# Layer_4.net
KiCad netlist of a schematic drawn in EAGLE
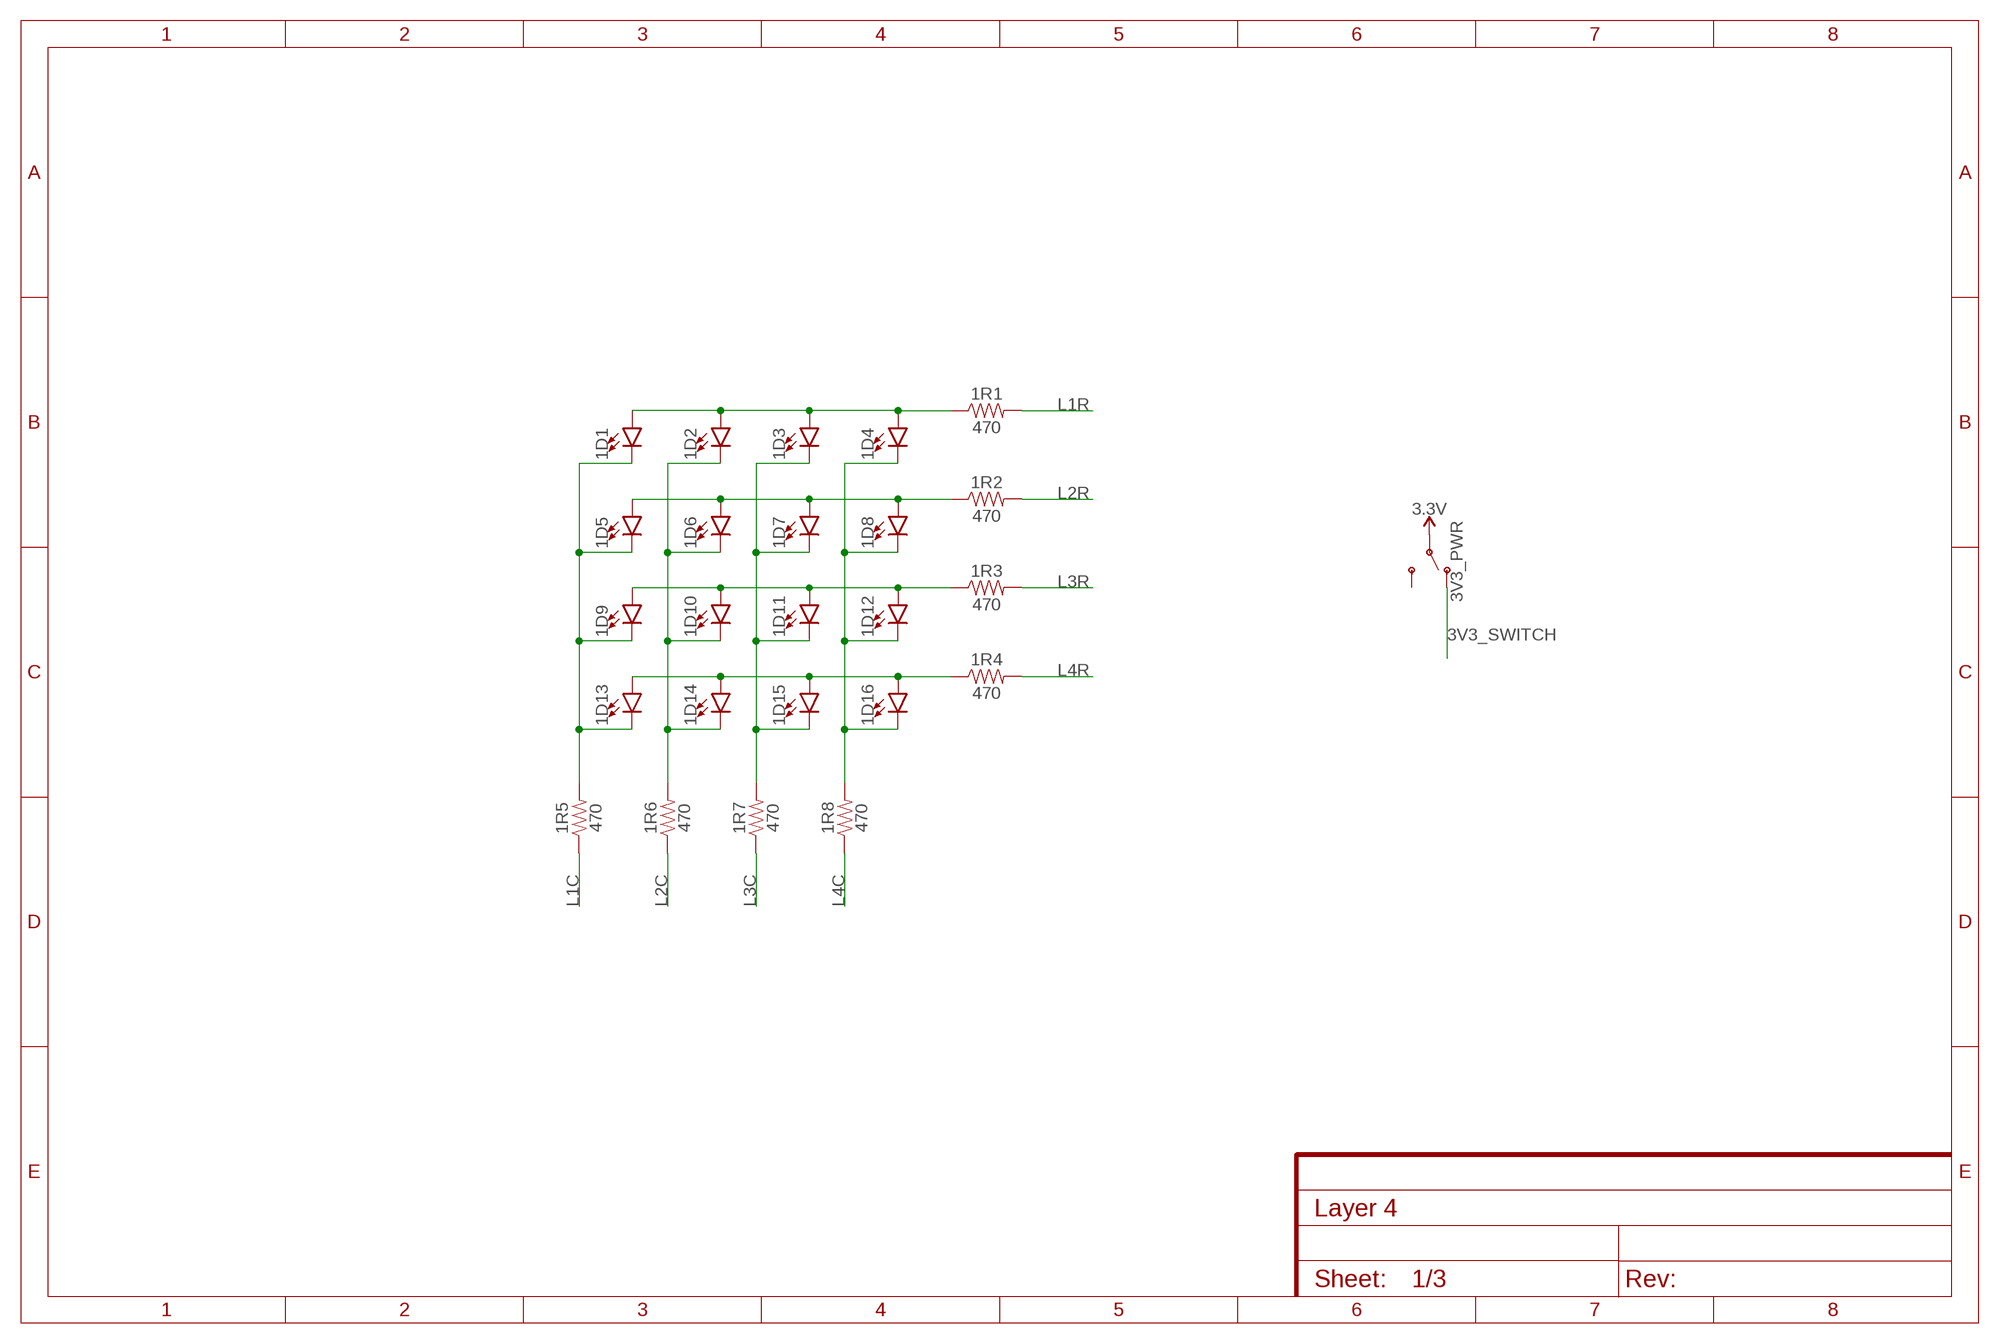
[diagram p0: schematic, sheet 1]
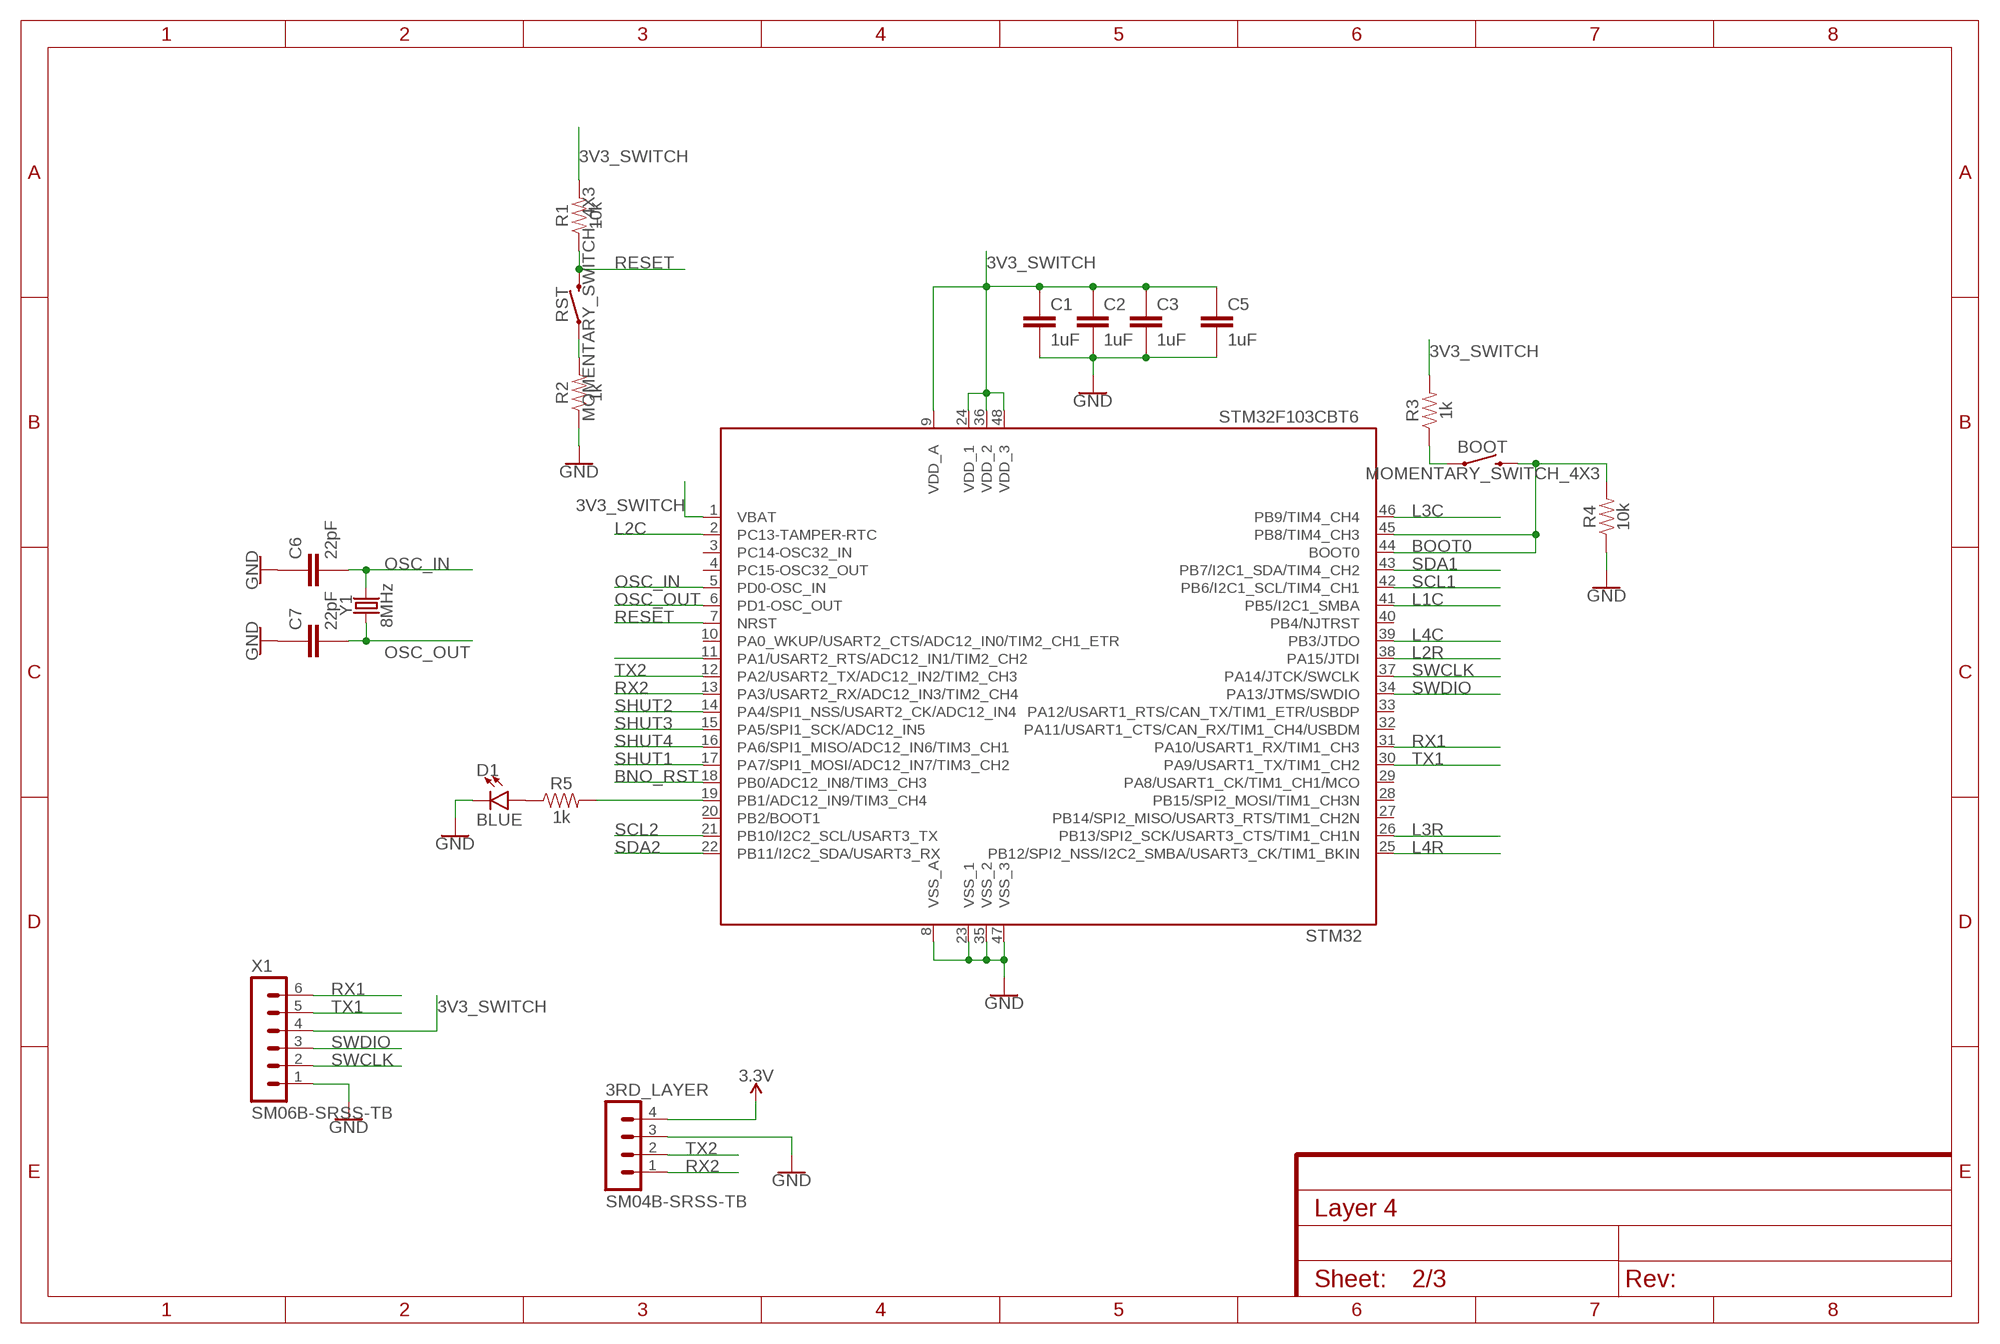
[diagram p1: schematic, sheet 2]
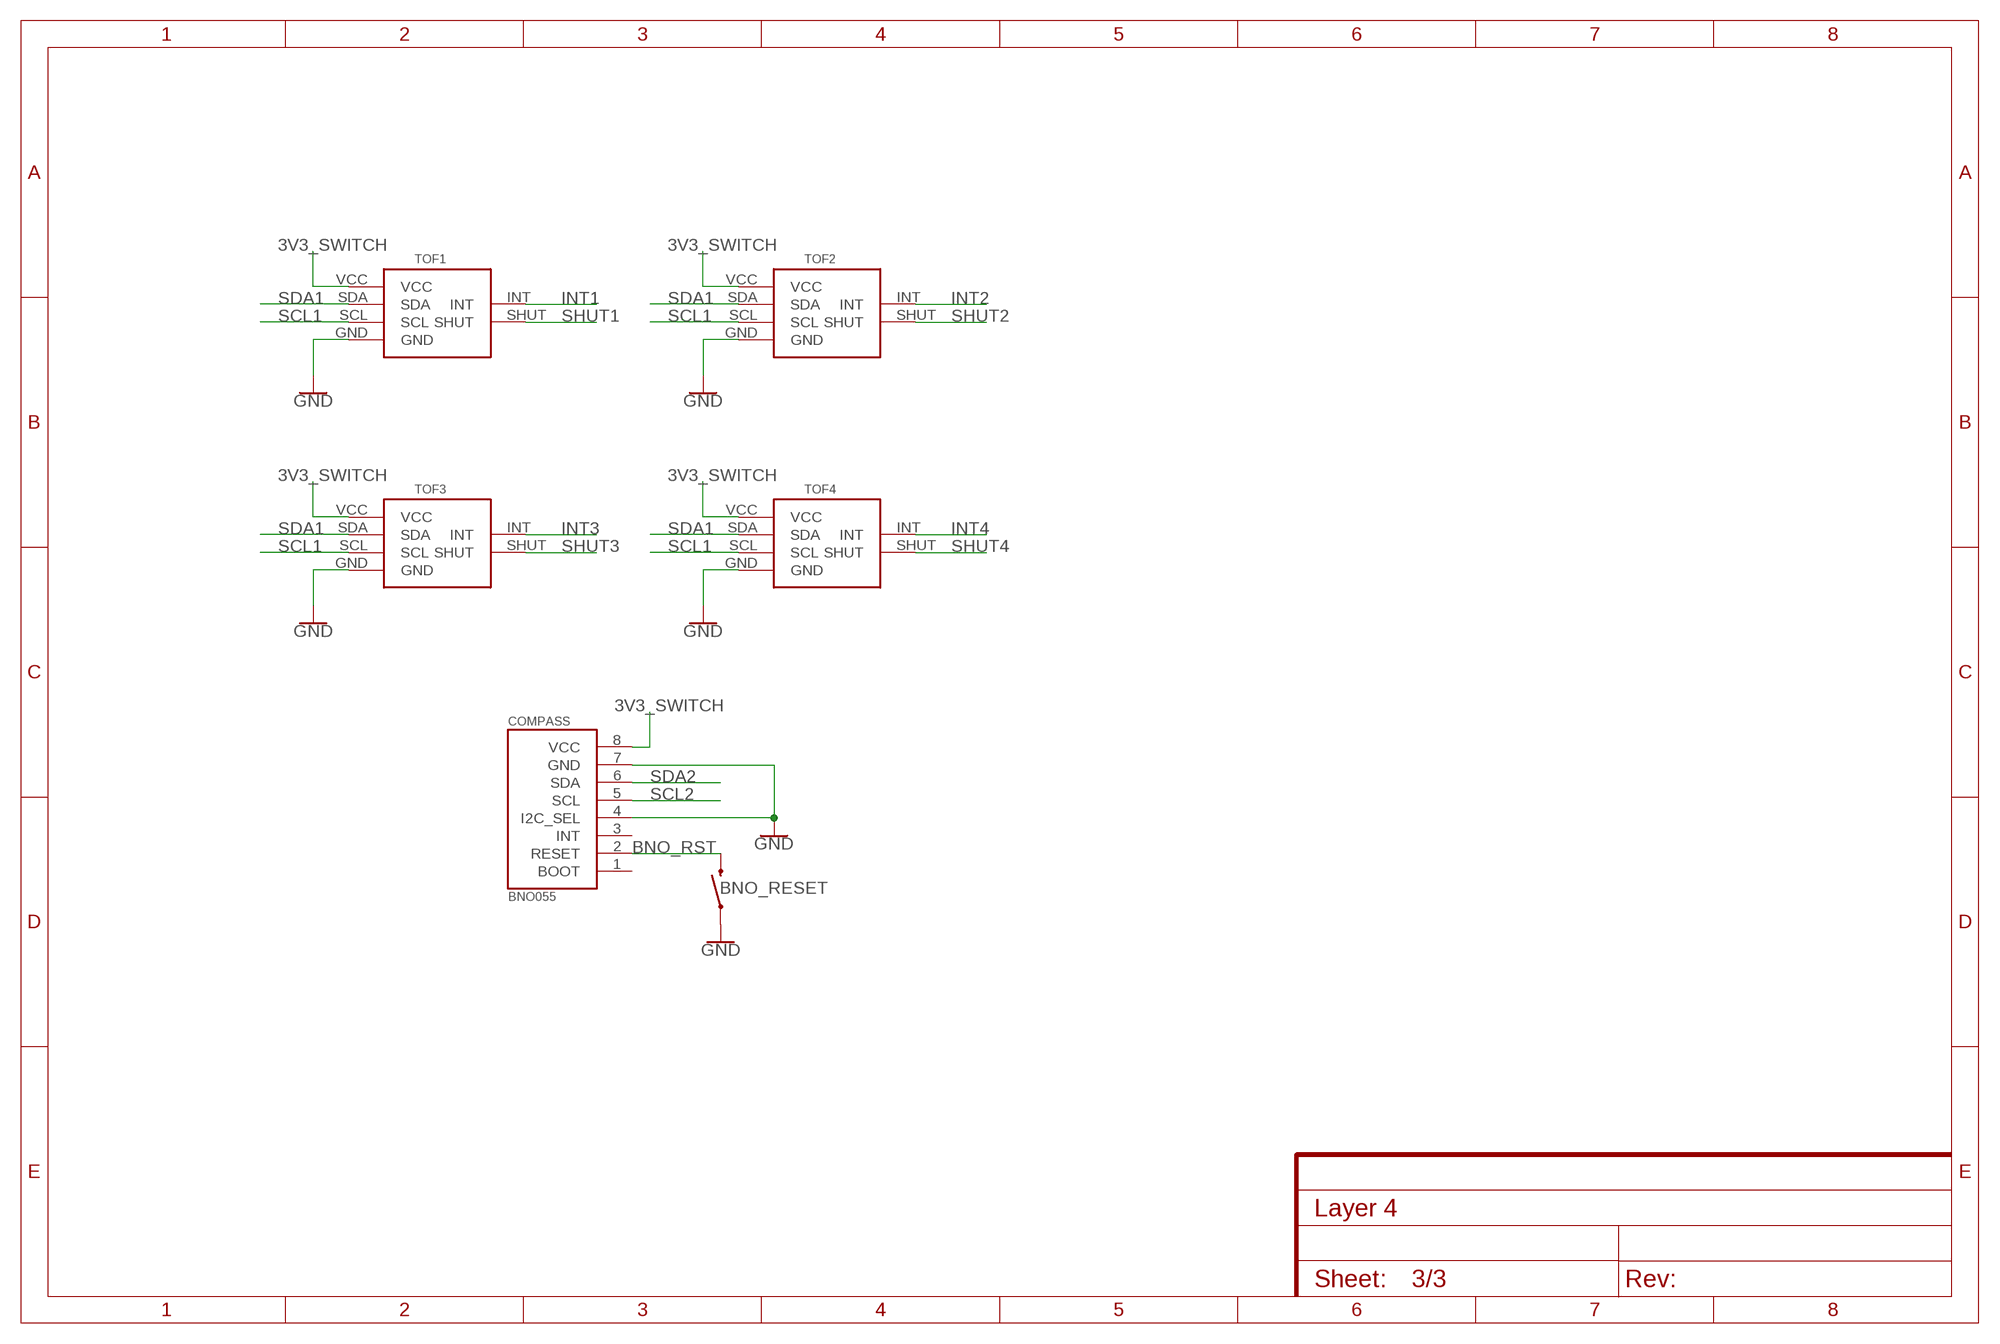
[diagram p2: schematic, sheet 3]

(export (version "E")
  (design (tool "Eeschema 10.0.6"))
  (components
    (comp (ref "BNO_RESET")
      (value "MOMENTARY_SWITCH_4X3")
      (footprint "eagle-import:MOMENTARY_SWITCH_4X3")
      (libsource (lib "eagle-import") (part "MOMENTARY_SWITCH_4X3"))
    )
    (comp (ref "COMPASS")
      (value "BNO055")
      (footprint "eagle-import:BNO055")
      (libsource (lib "eagle-import") (part "BNO055"))
    )
    (comp (ref "TOF1")
      (value "VL53L1X")
      (footprint "eagle-import:VL53L1X_SLANTEDPINS")
      (libsource (lib "eagle-import") (part "VL53L1X"))
    )
    (comp (ref "TOF2")
      (value "VL53L1X")
      (footprint "eagle-import:VL53L1X_SLANTEDPINS")
      (libsource (lib "eagle-import") (part "VL53L1X"))
    )
    (comp (ref "TOF3")
      (value "VL53L1X")
      (footprint "eagle-import:VL53L1X_SLANTEDPINS")
      (libsource (lib "eagle-import") (part "VL53L1X"))
    )
    (comp (ref "TOF4")
      (value "VL53L1X")
      (footprint "eagle-import:VL53L1X_SLANTEDPINS")
      (libsource (lib "eagle-import") (part "VL53L1X"))
    )
    (comp (ref "1D1")
      (value "LED0603")
      (footprint "eagle-import:LED-0603")
      (libsource (lib "eagle-import") (part "LED0603"))
    )
    (comp (ref "1D2")
      (value "LED0603")
      (footprint "eagle-import:LED-0603")
      (libsource (lib "eagle-import") (part "LED0603"))
    )
    (comp (ref "1D3")
      (value "LED0603")
      (footprint "eagle-import:LED-0603")
      (libsource (lib "eagle-import") (part "LED0603"))
    )
    (comp (ref "1D4")
      (value "LED0603")
      (footprint "eagle-import:LED-0603")
      (libsource (lib "eagle-import") (part "LED0603"))
    )
    (comp (ref "1D5")
      (value "LED0603")
      (footprint "eagle-import:LED-0603")
      (libsource (lib "eagle-import") (part "LED0603"))
    )
    (comp (ref "1D6")
      (value "LED0603")
      (footprint "eagle-import:LED-0603")
      (libsource (lib "eagle-import") (part "LED0603"))
    )
    (comp (ref "1D7")
      (value "LED0603")
      (footprint "eagle-import:LED-0603")
      (libsource (lib "eagle-import") (part "LED0603"))
    )
    (comp (ref "1D8")
      (value "LED0603")
      (footprint "eagle-import:LED-0603")
      (libsource (lib "eagle-import") (part "LED0603"))
    )
    (comp (ref "1D9")
      (value "LED0603")
      (footprint "eagle-import:LED-0603")
      (libsource (lib "eagle-import") (part "LED0603"))
    )
    (comp (ref "1D10")
      (value "LED0603")
      (footprint "eagle-import:LED-0603")
      (libsource (lib "eagle-import") (part "LED0603"))
    )
    (comp (ref "1D11")
      (value "LED0603")
      (footprint "eagle-import:LED-0603")
      (libsource (lib "eagle-import") (part "LED0603"))
    )
    (comp (ref "1D12")
      (value "LED0603")
      (footprint "eagle-import:LED-0603")
      (libsource (lib "eagle-import") (part "LED0603"))
    )
    (comp (ref "1D13")
      (value "LED0603")
      (footprint "eagle-import:LED-0603")
      (libsource (lib "eagle-import") (part "LED0603"))
    )
    (comp (ref "1D14")
      (value "LED0603")
      (footprint "eagle-import:LED-0603")
      (libsource (lib "eagle-import") (part "LED0603"))
    )
    (comp (ref "1D15")
      (value "LED0603")
      (footprint "eagle-import:LED-0603")
      (libsource (lib "eagle-import") (part "LED0603"))
    )
    (comp (ref "1D16")
      (value "LED0603")
      (footprint "eagle-import:LED-0603")
      (libsource (lib "eagle-import") (part "LED0603"))
    )
    (comp (ref "1R1")
      (value "470")
      (footprint "eagle-import:R0603")
      (libsource (lib "eagle-import") (part "RESISTOR0603"))
    )
    (comp (ref "1R2")
      (value "470")
      (footprint "eagle-import:R0603")
      (libsource (lib "eagle-import") (part "RESISTOR0603"))
    )
    (comp (ref "1R3")
      (value "470")
      (footprint "eagle-import:R0603")
      (libsource (lib "eagle-import") (part "RESISTOR0603"))
    )
    (comp (ref "1R4")
      (value "470")
      (footprint "eagle-import:R0603")
      (libsource (lib "eagle-import") (part "RESISTOR0603"))
    )
    (comp (ref "1R5")
      (value "470")
      (footprint "eagle-import:R0603")
      (libsource (lib "eagle-import") (part "RESISTOR0603"))
    )
    (comp (ref "1R6")
      (value "470")
      (footprint "eagle-import:R0603")
      (libsource (lib "eagle-import") (part "RESISTOR0603"))
    )
    (comp (ref "1R7")
      (value "470")
      (footprint "eagle-import:R0603")
      (libsource (lib "eagle-import") (part "RESISTOR0603"))
    )
    (comp (ref "1R8")
      (value "470")
      (footprint "eagle-import:R0603")
      (libsource (lib "eagle-import") (part "RESISTOR0603"))
    )
    (comp (ref "3V3_PWR")
      (value "SWITCH-SPDT-PTH-11.6X4.0MM-LOCK")
      (footprint "eagle-import:SWITCH_SPDT_PTH_11.6X4.0MM_LOCK")
      (libsource (lib "eagle-import") (part "SWITCH-SPDT-PTH-11.6X4.0MM-LOCK"))
    )
    (comp (ref "3RD_LAYER")
      (value "SM04B-SRSS-TB")
      (footprint "eagle-import:SM04B-SRSS-TB")
      (libsource (lib "eagle-import") (part "SM04B-SRSS-TB"))
    )
    (comp (ref "BOOT")
      (value "MOMENTARY_SWITCH_4X3")
      (footprint "eagle-import:MOMENTARY_SWITCH_4X3")
      (libsource (lib "eagle-import") (part "MOMENTARY_SWITCH_4X3"))
    )
    (comp (ref "C1")
      (value "1uF")
      (footprint "eagle-import:C0603")
      (libsource (lib "eagle-import") (part "CAPACITOR0603"))
    )
    (comp (ref "C2")
      (value "1uF")
      (footprint "eagle-import:C0603")
      (libsource (lib "eagle-import") (part "CAPACITOR0603"))
    )
    (comp (ref "C3")
      (value "1uF")
      (footprint "eagle-import:C0603")
      (libsource (lib "eagle-import") (part "CAPACITOR0603"))
    )
    (comp (ref "C5")
      (value "1uF")
      (footprint "eagle-import:C0603")
      (libsource (lib "eagle-import") (part "CAPACITOR0603"))
    )
    (comp (ref "C6")
      (value "22pF")
      (footprint "eagle-import:C0603")
      (libsource (lib "eagle-import") (part "CAPACITOR0603"))
    )
    (comp (ref "C7")
      (value "22pF")
      (footprint "eagle-import:C0603")
      (libsource (lib "eagle-import") (part "CAPACITOR0603"))
    )
    (comp (ref "D1")
      (value "BLUE")
      (footprint "eagle-import:LED-0603")
      (libsource (lib "eagle-import") (part "LED0603"))
    )
    (comp (ref "R1")
      (value "10k")
      (footprint "eagle-import:R0603")
      (libsource (lib "eagle-import") (part "RESISTOR0603"))
    )
    (comp (ref "R2")
      (value "1k")
      (footprint "eagle-import:R0603")
      (libsource (lib "eagle-import") (part "RESISTOR0603"))
    )
    (comp (ref "R3")
      (value "1k")
      (footprint "eagle-import:R0603")
      (libsource (lib "eagle-import") (part "RESISTOR0603"))
    )
    (comp (ref "R4")
      (value "10k")
      (footprint "eagle-import:R0603")
      (libsource (lib "eagle-import") (part "RESISTOR0603"))
    )
    (comp (ref "R5")
      (value "1k")
      (footprint "eagle-import:R0603")
      (libsource (lib "eagle-import") (part "RESISTOR0603"))
    )
    (comp (ref "RST")
      (value "MOMENTARY_SWITCH_4X3")
      (footprint "eagle-import:MOMENTARY_SWITCH_4X3")
      (libsource (lib "eagle-import") (part "MOMENTARY_SWITCH_4X3"))
    )
    (comp (ref "STM32")
      (value "STM32F103CBT6")
      (footprint "eagle-import:LQFP48")
      (libsource (lib "eagle-import") (part "STM32F103CBT6"))
    )
    (comp (ref "X1")
      (value "SM06B-SRSS-TB")
      (footprint "eagle-import:SM06B-SRSS-TB")
      (libsource (lib "eagle-import") (part "SM06B-SRSS-TB"))
    )
    (comp (ref "Y1")
      (value "8MHz")
      (footprint "eagle-import:CRYSTAL-SMD-5X3.2-2PAD")
      (libsource (lib "eagle-import") (part "CRYSTALSMD-5X3.2-2PAD"))
    )
  )
  (nets
    (net (code "1") (name "3.3V") (class "Default")
      (node (ref "3RD_LAYER") (pin "4") (pinfunction "4_4") (pintype "passive"))
      (node (ref "3V3_PWR") (pin "2") (pinfunction "P_2") (pintype "passive"))
    )
    (net (code "2") (name "3V3_SWITCH") (class "Default")
      (node (ref "3V3_PWR") (pin "1") (pinfunction "O_1") (pintype "passive"))
      (node (ref "C1") (pin "1") (pinfunction "1_1") (pintype "passive"))
      (node (ref "C2") (pin "1") (pinfunction "1_1") (pintype "passive"))
      (node (ref "C3") (pin "1") (pinfunction "1_1") (pintype "passive"))
      (node (ref "C5") (pin "2") (pinfunction "2_2") (pintype "passive"))
      (node (ref "COMPASS") (pin "8") (pinfunction "VCC_8") (pintype "bidirectional"))
      (node (ref "R1") (pin "2") (pinfunction "2_2") (pintype "passive"))
      (node (ref "R3") (pin "2") (pinfunction "2_2") (pintype "passive"))
      (node (ref "STM32") (pin "1") (pinfunction "VBAT_1") (pintype "power_in"))
      (node (ref "STM32") (pin "24") (pinfunction "VDD_1_24") (pintype "power_in"))
      (node (ref "STM32") (pin "36") (pinfunction "VDD_2_36") (pintype "power_in"))
      (node (ref "STM32") (pin "48") (pinfunction "VDD_3_48") (pintype "power_in"))
      (node (ref "STM32") (pin "9") (pinfunction "VDD_A_9") (pintype "power_in"))
      (node (ref "TOF1") (pin "VCC") (pinfunction "VCC_VCC") (pintype "power_in"))
      (node (ref "TOF2") (pin "VCC") (pinfunction "VCC_VCC") (pintype "power_in"))
      (node (ref "TOF3") (pin "VCC") (pinfunction "VCC_VCC") (pintype "power_in"))
      (node (ref "TOF4") (pin "VCC") (pinfunction "VCC_VCC") (pintype "power_in"))
      (node (ref "X1") (pin "4") (pinfunction "4_4") (pintype "passive"))
    )
    (net (code "3") (name "BNO_RST") (class "Default")
      (node (ref "BNO_RESET") (pin "P$2") (pinfunction "2_P$2") (pintype "passive"))
      (node (ref "COMPASS") (pin "2") (pinfunction "RESET_2") (pintype "bidirectional"))
      (node (ref "STM32") (pin "18") (pinfunction "PB0/ADC12_IN8/TIM3_CH3_18") (pintype "bidirectional"))
    )
    (net (code "4") (name "BOOT0") (class "Default")
      (node (ref "BOOT") (pin "P$2") (pinfunction "2_P$2") (pintype "passive"))
      (node (ref "R4") (pin "2") (pinfunction "2_2") (pintype "passive"))
      (node (ref "STM32") (pin "44") (pinfunction "BOOT0_44") (pintype "input"))
      (node (ref "STM32") (pin "45") (pinfunction "PB8/TIM4_CH3_45") (pintype "bidirectional"))
    )
    (net (code "5") (name "GND") (class "Default")
      (node (ref "3RD_LAYER") (pin "3") (pinfunction "3_3") (pintype "passive"))
      (node (ref "BNO_RESET") (pin "P$1") (pinfunction "1_P$1") (pintype "passive"))
      (node (ref "C1") (pin "2") (pinfunction "2_2") (pintype "passive"))
      (node (ref "C2") (pin "2") (pinfunction "2_2") (pintype "passive"))
      (node (ref "C3") (pin "2") (pinfunction "2_2") (pintype "passive"))
      (node (ref "C5") (pin "1") (pinfunction "1_1") (pintype "passive"))
      (node (ref "C6") (pin "1") (pinfunction "1_1") (pintype "passive"))
      (node (ref "C7") (pin "1") (pinfunction "1_1") (pintype "passive"))
      (node (ref "COMPASS") (pin "4") (pinfunction "I2C_SEL_4") (pintype "bidirectional"))
      (node (ref "COMPASS") (pin "7") (pinfunction "GND_7") (pintype "bidirectional"))
      (node (ref "D1") (pin "C") (pinfunction "C_C") (pintype "passive"))
      (node (ref "R2") (pin "1") (pinfunction "1_1") (pintype "passive"))
      (node (ref "R4") (pin "1") (pinfunction "1_1") (pintype "passive"))
      (node (ref "STM32") (pin "23") (pinfunction "VSS_1_23") (pintype "power_in"))
      (node (ref "STM32") (pin "35") (pinfunction "VSS_2_35") (pintype "power_in"))
      (node (ref "STM32") (pin "47") (pinfunction "VSS_3_47") (pintype "power_in"))
      (node (ref "STM32") (pin "8") (pinfunction "VSS_A_8") (pintype "power_in"))
      (node (ref "TOF1") (pin "GND") (pinfunction "GND_GND") (pintype "power_in"))
      (node (ref "TOF2") (pin "GND") (pinfunction "GND_GND") (pintype "power_in"))
      (node (ref "TOF3") (pin "GND") (pinfunction "GND_GND") (pintype "power_in"))
      (node (ref "TOF4") (pin "GND") (pinfunction "GND_GND") (pintype "power_in"))
      (node (ref "X1") (pin "1") (pinfunction "1_1") (pintype "passive"))
    )
    (net (code "6") (name "INT1") (class "Default")
      (node (ref "TOF1") (pin "INT") (pinfunction "INT_INT") (pintype "bidirectional"))
    )
    (net (code "7") (name "INT2") (class "Default")
      (node (ref "TOF2") (pin "INT") (pinfunction "INT_INT") (pintype "bidirectional"))
    )
    (net (code "8") (name "INT3") (class "Default")
      (node (ref "TOF3") (pin "INT") (pinfunction "INT_INT") (pintype "bidirectional"))
    )
    (net (code "9") (name "INT4") (class "Default")
      (node (ref "TOF4") (pin "INT") (pinfunction "INT_INT") (pintype "bidirectional"))
    )
    (net (code "10") (name "L1C") (class "Default")
      (node (ref "1R5") (pin "1") (pinfunction "1_1") (pintype "passive"))
      (node (ref "STM32") (pin "41") (pinfunction "PB5/I2C1_SMBA_41") (pintype "input"))
    )
    (net (code "11") (name "L1R") (class "Default")
      (node (ref "1R1") (pin "2") (pinfunction "2_2") (pintype "passive"))
      (node (ref "STM32") (pin "11") (pinfunction "PA1/USART2_RTS/ADC12_IN1/TIM2_CH2_11") (pintype "bidirectional"))
    )
    (net (code "12") (name "L2C") (class "Default")
      (node (ref "1R6") (pin "1") (pinfunction "1_1") (pintype "passive"))
      (node (ref "STM32") (pin "2") (pinfunction "PC13-TAMPER-RTC_2") (pintype "input"))
    )
    (net (code "13") (name "L2R") (class "Default")
      (node (ref "1R2") (pin "2") (pinfunction "2_2") (pintype "passive"))
      (node (ref "STM32") (pin "38") (pinfunction "PA15/JTDI_38") (pintype "bidirectional"))
    )
    (net (code "14") (name "L3C") (class "Default")
      (node (ref "1R7") (pin "1") (pinfunction "1_1") (pintype "passive"))
      (node (ref "STM32") (pin "46") (pinfunction "PB9/TIM4_CH4_46") (pintype "input"))
    )
    (net (code "15") (name "L3R") (class "Default")
      (node (ref "1R3") (pin "2") (pinfunction "2_2") (pintype "passive"))
      (node (ref "STM32") (pin "26") (pinfunction "PB13/SPI2_SCK/USART3_CTS/TIM1_CH1N_26") (pintype "input"))
    )
    (net (code "16") (name "L4C") (class "Default")
      (node (ref "1R8") (pin "1") (pinfunction "1_1") (pintype "passive"))
      (node (ref "STM32") (pin "39") (pinfunction "PB3/JTDO_39") (pintype "bidirectional"))
    )
    (net (code "17") (name "L4R") (class "Default")
      (node (ref "1R4") (pin "2") (pinfunction "2_2") (pintype "passive"))
      (node (ref "STM32") (pin "25") (pinfunction "PB12/SPI2_NSS/I2C2_SMBA/USART3_CK/TIM1_BKIN_25") (pintype "input"))
    )
    (net (code "18") (name "Net-(1D1-PadA)") (class "Default")
      (node (ref "1D1") (pin "A") (pinfunction "A_A") (pintype "passive"))
      (node (ref "1D2") (pin "A") (pinfunction "A_A") (pintype "passive"))
      (node (ref "1D3") (pin "A") (pinfunction "A_A") (pintype "passive"))
      (node (ref "1D4") (pin "A") (pinfunction "A_A") (pintype "passive"))
      (node (ref "1R1") (pin "1") (pinfunction "1_1") (pintype "passive"))
    )
    (net (code "19") (name "Net-(1D1-PadC)") (class "Default")
      (node (ref "1D1") (pin "C") (pinfunction "C_C") (pintype "passive"))
      (node (ref "1D13") (pin "C") (pinfunction "C_C") (pintype "passive"))
      (node (ref "1D5") (pin "C") (pinfunction "C_C") (pintype "passive"))
      (node (ref "1D9") (pin "C") (pinfunction "C_C") (pintype "passive"))
      (node (ref "1R5") (pin "2") (pinfunction "2_2") (pintype "passive"))
    )
    (net (code "20") (name "Net-(1D5-PadA)") (class "Default")
      (node (ref "1D5") (pin "A") (pinfunction "A_A") (pintype "passive"))
      (node (ref "1D6") (pin "A") (pinfunction "A_A") (pintype "passive"))
      (node (ref "1D7") (pin "A") (pinfunction "A_A") (pintype "passive"))
      (node (ref "1D8") (pin "A") (pinfunction "A_A") (pintype "passive"))
      (node (ref "1R2") (pin "1") (pinfunction "1_1") (pintype "passive"))
    )
    (net (code "21") (name "Net-(1D10-PadA)") (class "Default")
      (node (ref "1D10") (pin "A") (pinfunction "A_A") (pintype "passive"))
      (node (ref "1D11") (pin "A") (pinfunction "A_A") (pintype "passive"))
      (node (ref "1D12") (pin "A") (pinfunction "A_A") (pintype "passive"))
      (node (ref "1D9") (pin "A") (pinfunction "A_A") (pintype "passive"))
      (node (ref "1R3") (pin "1") (pinfunction "1_1") (pintype "passive"))
    )
    (net (code "22") (name "Net-(1D10-PadC)") (class "Default")
      (node (ref "1D10") (pin "C") (pinfunction "C_C") (pintype "passive"))
      (node (ref "1D14") (pin "C") (pinfunction "C_C") (pintype "passive"))
      (node (ref "1D2") (pin "C") (pinfunction "C_C") (pintype "passive"))
      (node (ref "1D6") (pin "C") (pinfunction "C_C") (pintype "passive"))
      (node (ref "1R6") (pin "2") (pinfunction "2_2") (pintype "passive"))
    )
    (net (code "23") (name "Net-(1D11-PadC)") (class "Default")
      (node (ref "1D11") (pin "C") (pinfunction "C_C") (pintype "passive"))
      (node (ref "1D15") (pin "C") (pinfunction "C_C") (pintype "passive"))
      (node (ref "1D3") (pin "C") (pinfunction "C_C") (pintype "passive"))
      (node (ref "1D7") (pin "C") (pinfunction "C_C") (pintype "passive"))
      (node (ref "1R7") (pin "2") (pinfunction "2_2") (pintype "passive"))
    )
    (net (code "24") (name "Net-(1D12-PadC)") (class "Default")
      (node (ref "1D12") (pin "C") (pinfunction "C_C") (pintype "passive"))
      (node (ref "1D16") (pin "C") (pinfunction "C_C") (pintype "passive"))
      (node (ref "1D4") (pin "C") (pinfunction "C_C") (pintype "passive"))
      (node (ref "1D8") (pin "C") (pinfunction "C_C") (pintype "passive"))
      (node (ref "1R8") (pin "2") (pinfunction "2_2") (pintype "passive"))
    )
    (net (code "25") (name "Net-(1D13-PadA)") (class "Default")
      (node (ref "1D13") (pin "A") (pinfunction "A_A") (pintype "passive"))
      (node (ref "1D14") (pin "A") (pinfunction "A_A") (pintype "passive"))
      (node (ref "1D15") (pin "A") (pinfunction "A_A") (pintype "passive"))
      (node (ref "1D16") (pin "A") (pinfunction "A_A") (pintype "passive"))
      (node (ref "1R4") (pin "1") (pinfunction "1_1") (pintype "passive"))
    )
    (net (code "26") (name "Net-(BOOT-1)") (class "Default")
      (node (ref "BOOT") (pin "P$1") (pinfunction "1_P$1") (pintype "passive"))
      (node (ref "R3") (pin "1") (pinfunction "1_1") (pintype "passive"))
    )
    (net (code "27") (name "Net-(D1-PadA)") (class "Default")
      (node (ref "D1") (pin "A") (pinfunction "A_A") (pintype "passive"))
      (node (ref "R5") (pin "1") (pinfunction "1_1") (pintype "passive"))
    )
    (net (code "28") (name "Net-(RST-1)") (class "Default")
      (node (ref "R2") (pin "2") (pinfunction "2_2") (pintype "passive"))
      (node (ref "RST") (pin "P$1") (pinfunction "1_P$1") (pintype "passive"))
    )
    (net (code "29") (name "Net-(STM32-PB1{slash}ADC12_IN9{slash}TIM3_CH4)") (class "Default")
      (node (ref "R5") (pin "2") (pinfunction "2_2") (pintype "passive"))
      (node (ref "STM32") (pin "19") (pinfunction "PB1/ADC12_IN9/TIM3_CH4_19") (pintype "bidirectional"))
    )
    (net (code "30") (name "OSC_IN") (class "Default")
      (node (ref "C6") (pin "2") (pinfunction "2_2") (pintype "passive"))
      (node (ref "STM32") (pin "5") (pinfunction "PD0-OSC_IN_5") (pintype "input"))
      (node (ref "Y1") (pin "P$2") (pinfunction "2_P$2") (pintype "passive"))
    )
    (net (code "31") (name "OSC_OUT") (class "Default")
      (node (ref "C7") (pin "2") (pinfunction "2_2") (pintype "passive"))
      (node (ref "STM32") (pin "6") (pinfunction "PD1-OSC_OUT_6") (pintype "input"))
      (node (ref "Y1") (pin "P$1") (pinfunction "1_P$1") (pintype "passive"))
    )
    (net (code "32") (name "RESET") (class "Default")
      (node (ref "R1") (pin "1") (pinfunction "1_1") (pintype "passive"))
      (node (ref "RST") (pin "P$2") (pinfunction "2_P$2") (pintype "passive"))
      (node (ref "STM32") (pin "7") (pinfunction "NRST_7") (pintype "input"))
    )
    (net (code "33") (name "RX1") (class "Default")
      (node (ref "STM32") (pin "31") (pinfunction "PA10/USART1_RX/TIM1_CH3_31") (pintype "bidirectional"))
      (node (ref "X1") (pin "6") (pinfunction "6_6") (pintype "passive"))
    )
    (net (code "34") (name "RX2") (class "Default")
      (node (ref "3RD_LAYER") (pin "1") (pinfunction "1_1") (pintype "passive"))
      (node (ref "STM32") (pin "13") (pinfunction "PA3/USART2_RX/ADC12_IN3/TIM2_CH4_13") (pintype "bidirectional"))
    )
    (net (code "35") (name "SCL1") (class "Default")
      (node (ref "STM32") (pin "42") (pinfunction "PB6/I2C1_SCL/TIM4_CH1_42") (pintype "input"))
      (node (ref "TOF1") (pin "SCL") (pinfunction "SCL_SCL") (pintype "bidirectional"))
      (node (ref "TOF2") (pin "SCL") (pinfunction "SCL_SCL") (pintype "bidirectional"))
      (node (ref "TOF3") (pin "SCL") (pinfunction "SCL_SCL") (pintype "bidirectional"))
      (node (ref "TOF4") (pin "SCL") (pinfunction "SCL_SCL") (pintype "bidirectional"))
    )
    (net (code "36") (name "SCL2") (class "Default")
      (node (ref "COMPASS") (pin "5") (pinfunction "SCL_5") (pintype "bidirectional"))
      (node (ref "STM32") (pin "21") (pinfunction "PB10/I2C2_SCL/USART3_TX_21") (pintype "input"))
    )
    (net (code "37") (name "SDA1") (class "Default")
      (node (ref "STM32") (pin "43") (pinfunction "PB7/I2C1_SDA/TIM4_CH2_43") (pintype "bidirectional"))
      (node (ref "TOF1") (pin "SDA") (pinfunction "SDA_SDA") (pintype "bidirectional"))
      (node (ref "TOF2") (pin "SDA") (pinfunction "SDA_SDA") (pintype "bidirectional"))
      (node (ref "TOF3") (pin "SDA") (pinfunction "SDA_SDA") (pintype "bidirectional"))
      (node (ref "TOF4") (pin "SDA") (pinfunction "SDA_SDA") (pintype "bidirectional"))
    )
    (net (code "38") (name "SDA2") (class "Default")
      (node (ref "COMPASS") (pin "6") (pinfunction "SDA_6") (pintype "bidirectional"))
      (node (ref "STM32") (pin "22") (pinfunction "PB11/I2C2_SDA/USART3_RX_22") (pintype "input"))
    )
    (net (code "39") (name "SHUT1") (class "Default")
      (node (ref "STM32") (pin "17") (pinfunction "PA7/SPI1_MOSI/ADC12_IN7/TIM3_CH2_17") (pintype "bidirectional"))
      (node (ref "TOF1") (pin "SHUT") (pinfunction "SHUT_SHUT") (pintype "bidirectional"))
    )
    (net (code "40") (name "SHUT2") (class "Default")
      (node (ref "STM32") (pin "14") (pinfunction "PA4/SPI1_NSS/USART2_CK/ADC12_IN4_14") (pintype "bidirectional"))
      (node (ref "TOF2") (pin "SHUT") (pinfunction "SHUT_SHUT") (pintype "bidirectional"))
    )
    (net (code "41") (name "SHUT3") (class "Default")
      (node (ref "STM32") (pin "15") (pinfunction "PA5/SPI1_SCK/ADC12_IN5_15") (pintype "bidirectional"))
      (node (ref "TOF3") (pin "SHUT") (pinfunction "SHUT_SHUT") (pintype "bidirectional"))
    )
    (net (code "42") (name "SHUT4") (class "Default")
      (node (ref "STM32") (pin "16") (pinfunction "PA6/SPI1_MISO/ADC12_IN6/TIM3_CH1_16") (pintype "bidirectional"))
      (node (ref "TOF4") (pin "SHUT") (pinfunction "SHUT_SHUT") (pintype "bidirectional"))
    )
    (net (code "43") (name "SWCLK") (class "Default")
      (node (ref "STM32") (pin "37") (pinfunction "PA14/JTCK/SWCLK_37") (pintype "bidirectional"))
      (node (ref "X1") (pin "2") (pinfunction "2_2") (pintype "passive"))
    )
    (net (code "44") (name "SWDIO") (class "Default")
      (node (ref "STM32") (pin "34") (pinfunction "PA13/JTMS/SWDIO_34") (pintype "bidirectional"))
      (node (ref "X1") (pin "3") (pinfunction "3_3") (pintype "passive"))
    )
    (net (code "45") (name "TX1") (class "Default")
      (node (ref "STM32") (pin "30") (pinfunction "PA9/USART1_TX/TIM1_CH2_30") (pintype "input"))
      (node (ref "X1") (pin "5") (pinfunction "5_5") (pintype "passive"))
    )
    (net (code "46") (name "TX2") (class "Default")
      (node (ref "3RD_LAYER") (pin "2") (pinfunction "2_2") (pintype "passive"))
      (node (ref "STM32") (pin "12") (pinfunction "PA2/USART2_TX/ADC12_IN2/TIM2_CH3_12") (pintype "bidirectional"))
    )
    (net (code "47") (name "unconnected-(3V3_PWR-S-Pad3)") (class "Default")
      (node (ref "3V3_PWR") (pin "3") (pinfunction "S_3") (pintype "passive"))
    )
    (net (code "48") (name "unconnected-(COMPASS-BOOT-Pad1)") (class "Default")
      (node (ref "COMPASS") (pin "1") (pinfunction "BOOT_1") (pintype "bidirectional"))
    )
    (net (code "49") (name "unconnected-(COMPASS-INT-Pad3)") (class "Default")
      (node (ref "COMPASS") (pin "3") (pinfunction "INT_3") (pintype "bidirectional"))
    )
    (net (code "50") (name "unconnected-(STM32-PA0_WKUP{slash}USART2_CTS{slash}ADC12_IN0{slash}TIM2_CH1_ETR-Pad10)") (class "Default")
      (node (ref "STM32") (pin "10") (pinfunction "PA0_WKUP/USART2_CTS/ADC12_IN0/TIM2_CH1_ETR_10") (pintype "bidirectional"))
    )
    (net (code "51") (name "unconnected-(STM32-PA8{slash}USART1_CK{slash}TIM1_CH1{slash}MCO-Pad29)") (class "Default")
      (node (ref "STM32") (pin "29") (pinfunction "PA8/USART1_CK/TIM1_CH1/MCO_29") (pintype "bidirectional"))
    )
    (net (code "52") (name "unconnected-(STM32-PA11{slash}USART1_CTS{slash}CAN_RX{slash}TIM1_CH4{slash}USBDM-Pad32)") (class "Default")
      (node (ref "STM32") (pin "32") (pinfunction "PA11/USART1_CTS/CAN_RX/TIM1_CH4/USBDM_32") (pintype "bidirectional"))
    )
    (net (code "53") (name "unconnected-(STM32-PA12{slash}USART1_RTS{slash}CAN_TX{slash}TIM1_ETR{slash}USBDP-Pad33)") (class "Default")
      (node (ref "STM32") (pin "33") (pinfunction "PA12/USART1_RTS/CAN_TX/TIM1_ETR/USBDP_33") (pintype "bidirectional"))
    )
    (net (code "54") (name "unconnected-(STM32-PB2{slash}BOOT1-Pad20)") (class "Default")
      (node (ref "STM32") (pin "20") (pinfunction "PB2/BOOT1_20") (pintype "bidirectional"))
    )
    (net (code "55") (name "unconnected-(STM32-PB4{slash}NJTRST-Pad40)") (class "Default")
      (node (ref "STM32") (pin "40") (pinfunction "PB4/NJTRST_40") (pintype "bidirectional"))
    )
    (net (code "56") (name "unconnected-(STM32-PB14{slash}SPI2_MISO{slash}USART3_RTS{slash}TIM1_CH2N-Pad27)") (class "Default")
      (node (ref "STM32") (pin "27") (pinfunction "PB14/SPI2_MISO/USART3_RTS/TIM1_CH2N_27") (pintype "input"))
    )
    (net (code "57") (name "unconnected-(STM32-PB15{slash}SPI2_MOSI{slash}TIM1_CH3N-Pad28)") (class "Default")
      (node (ref "STM32") (pin "28") (pinfunction "PB15/SPI2_MOSI/TIM1_CH3N_28") (pintype "input"))
    )
    (net (code "58") (name "unconnected-(STM32-PC14-OSC32_IN-Pad3)") (class "Default")
      (node (ref "STM32") (pin "3") (pinfunction "PC14-OSC32_IN_3") (pintype "input"))
    )
    (net (code "59") (name "unconnected-(STM32-PC15-OSC32_OUT-Pad4)") (class "Default")
      (node (ref "STM32") (pin "4") (pinfunction "PC15-OSC32_OUT_4") (pintype "input"))
    )
  )
)
